# Sheet1.net
KiCad netlist of a schematic drawn in Altium Designer
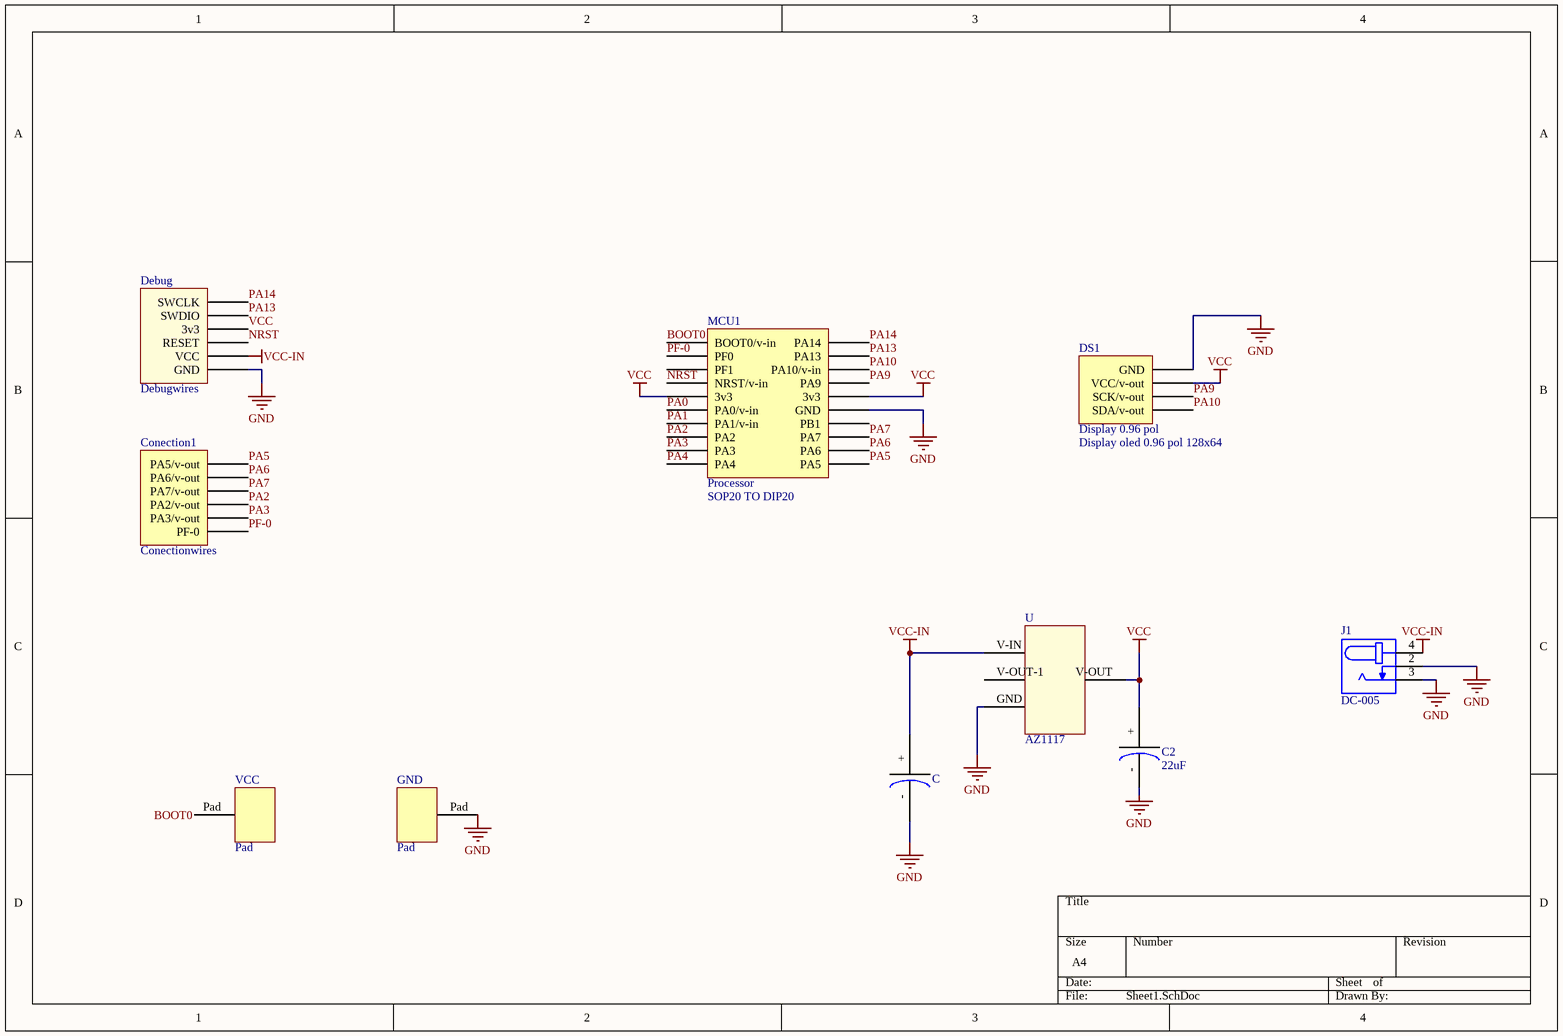
[diagram p0: Sheet1.SchDoc]

(export (version "E")
  (design (tool "Eeschema 10.0.6"))
  (components
    (comp (ref "C")
      (value "Capacitor Eletrolítico")
      (footprint "Capacitor")
      (libsource (lib "Schlib1") (part "Capacitor Eletrolítico"))
    )
    (comp (ref "C2")
      (value "22uF")
      (footprint "Capacitor")
      (libsource (lib "Schlib1") (part "Capacitor Eletrolítico"))
    )
    (comp (ref "Conection1")
      (value "Conectionwires")
      (footprint "Conectionwires")
      (description "6 out")
      (libsource (lib "Schlib1") (part "Conectionwires"))
    )
    (comp (ref "Debug")
      (value "Debugwires")
      (footprint "Debugwires")
      (description "2 in")
      (libsource (lib "Schlib1") (part "Debugwires"))
    )
    (comp (ref "DS1")
      (value "Display 0.96 pol")
      (footprint "Display oled")
      (description "0.96 pol 24.7x27 cm")
      (fields (field (name "INFORMATIONS") "Display oled 0.96 pol 128x64"))
      (libsource (lib "Schlib1") (part "Display oled"))
    )
    (comp (ref "GND") (value "Pad") (footprint "Pad") (libsource (lib "") (part "Pad_1")))
    (comp (ref "J1")
      (value "DC-005")
      (footprint "NINIGI_DC-005")
      (description "Polymeric PTC Resettable Fuse 15V 50mA Ih Surface Mount 0603 _1608 Metric_, Concave")
      (fields (field (name "MF") "Littelfuse Inc."))
      (libsource (lib "Schlib1") (part "DC-005"))
    )
    (comp (ref "MCU1")
      (value "Processor")
      (footprint "Processor")
      (description "Processor arm Stm32f0xx")
      (fields (field (name "ADAPTER") "SOP20 TO DIP20"))
      (libsource (lib "Schlib1") (part "Processor"))
    )
    (comp (ref "U")
      (value "AZ1117")
      (footprint "AZ1117")
      (description "Converter 5v to 3.3v")
      (libsource (lib "Schlib1") (part "AZ1117"))
    )
    (comp (ref "VCC") (value "Pad") (footprint "Pad") (libsource (lib "Schlib1") (part "Pad")))
  )
  (nets
    (net (code "1") (name "/BOOT0") (class "Default")
      (node (ref "MCU1") (pin "BOOT0") (pinfunction "BOOT0/v-in_BOOT0") (pintype "passive"))
      (node (ref "VCC") (pin "Pad") (pinfunction "Pad_Pad") (pintype "passive"))
    )
    (net (code "2") (name "/NRST") (class "Default")
      (node (ref "Debug") (pin "RESET") (pinfunction "RESET_RESET") (pintype "passive"))
      (node (ref "MCU1") (pin "NRST") (pinfunction "NRST/v-in_NRST") (pintype "passive"))
    )
    (net (code "3") (name "/PA0") (class "Default")
      (node (ref "MCU1") (pin "PA0") (pinfunction "PA0/v-in_PA0") (pintype "passive"))
    )
    (net (code "4") (name "/PA1") (class "Default")
      (node (ref "MCU1") (pin "PA1") (pinfunction "PA1/v-in_PA1") (pintype "passive"))
    )
    (net (code "5") (name "/PA2") (class "Default")
      (node (ref "Conection1") (pin "PA2") (pinfunction "PA2/v-out_PA2") (pintype "passive"))
      (node (ref "MCU1") (pin "PA2") (pinfunction "PA2_PA2") (pintype "passive"))
    )
    (net (code "6") (name "/PA3") (class "Default")
      (node (ref "Conection1") (pin "PA3") (pinfunction "PA3/v-out_PA3") (pintype "passive"))
      (node (ref "MCU1") (pin "PA3") (pinfunction "PA3_PA3") (pintype "passive"))
    )
    (net (code "7") (name "/PA4") (class "Default")
      (node (ref "MCU1") (pin "PA4") (pinfunction "PA4_PA4") (pintype "passive"))
    )
    (net (code "8") (name "/PA5") (class "Default")
      (node (ref "Conection1") (pin "PA5") (pinfunction "PA5/v-out_PA5") (pintype "passive"))
      (node (ref "MCU1") (pin "PA5") (pinfunction "PA5_PA5") (pintype "passive"))
    )
    (net (code "9") (name "/PA6") (class "Default")
      (node (ref "Conection1") (pin "PA6") (pinfunction "PA6/v-out_PA6") (pintype "passive"))
      (node (ref "MCU1") (pin "PA6") (pinfunction "PA6_PA6") (pintype "passive"))
    )
    (net (code "10") (name "/PA7") (class "Default")
      (node (ref "Conection1") (pin "PA7") (pinfunction "PA7/v-out_PA7") (pintype "passive"))
      (node (ref "MCU1") (pin "PA7") (pinfunction "PA7_PA7") (pintype "passive"))
    )
    (net (code "11") (name "/PA9") (class "Default")
      (node (ref "DS1") (pin "SCK") (pinfunction "SCK/v-out_SCK") (pintype "passive"))
      (node (ref "MCU1") (pin "PA9") (pinfunction "PA9_PA9") (pintype "passive"))
    )
    (net (code "12") (name "/PA10") (class "Default")
      (node (ref "DS1") (pin "SDA") (pinfunction "SDA/v-out_SDA") (pintype "passive"))
      (node (ref "MCU1") (pin "PA10") (pinfunction "PA10/v-in_PA10") (pintype "passive"))
    )
    (net (code "13") (name "/PA13") (class "Default")
      (node (ref "Debug") (pin "PA13") (pinfunction "SWDIO_PA13") (pintype "passive"))
      (node (ref "MCU1") (pin "PA13") (pinfunction "PA13_PA13") (pintype "passive"))
    )
    (net (code "14") (name "/PA14") (class "Default")
      (node (ref "Debug") (pin "PA14") (pinfunction "SWCLK_PA14") (pintype "passive"))
      (node (ref "MCU1") (pin "PA14") (pinfunction "PA14_PA14") (pintype "passive"))
    )
    (net (code "15") (name "/PF-0") (class "Default")
      (node (ref "Conection1") (pin "PF-0") (pinfunction "PF-0_PF-0") (pintype "passive"))
      (node (ref "MCU1") (pin "PF0") (pinfunction "PF0_PF0") (pintype "passive"))
    )
    (net (code "16") (name "GND") (class "Default")
      (node (ref "C") (pin "-") (pinfunction "-_-") (pintype "passive"))
      (node (ref "C2") (pin "-") (pinfunction "-_-") (pintype "passive"))
      (node (ref "DS1") (pin "GND") (pinfunction "GND_GND") (pintype "passive"))
      (node (ref "Debug") (pin "GND") (pinfunction "GND_GND") (pintype "passive"))
      (node (ref "GND") (pin "Pad") (pinfunction "Pad_Pad") (pintype "passive"))
      (node (ref "J1") (pin "2") (pinfunction "4_2") (pintype "passive"))
      (node (ref "J1") (pin "3") (pinfunction "3_3") (pintype "passive"))
      (node (ref "MCU1") (pin "GND") (pinfunction "GND_GND") (pintype "passive"))
      (node (ref "U") (pin "GND") (pinfunction "GND_GND") (pintype "passive"))
    )
    (net (code "17") (name "VCC") (class "Default")
      (node (ref "C2") (pin "+") (pinfunction "+_+") (pintype "passive"))
      (node (ref "DS1") (pin "VCC") (pinfunction "VCC/v-out_VCC") (pintype "passive"))
      (node (ref "Debug") (pin "3v3") (pinfunction "3v3_3v3") (pintype "passive"))
      (node (ref "MCU1") (pin "3v3") (pinfunction "3v3_3v3") (pintype "passive"))
      (node (ref "U") (pin "V-OUT") (pinfunction "V-OUT_V-OUT") (pintype "passive"))
    )
    (net (code "18") (name "VCC-IN") (class "Default")
      (node (ref "C") (pin "+") (pinfunction "+_+") (pintype "passive"))
      (node (ref "Debug") (pin "VCC") (pinfunction "VCC_VCC") (pintype "passive"))
      (node (ref "J1") (pin "4") (pinfunction "2_4") (pintype "passive"))
      (node (ref "U") (pin "V-IN") (pinfunction "V-IN_V-IN") (pintype "passive"))
    )
    (net (code "19") (name "unconnected-(MCU1-PadPB1)") (class "Default")
      (node (ref "MCU1") (pin "PB1") (pinfunction "PB1_PB1") (pintype "passive"))
    )
    (net (code "20") (name "unconnected-(MCU1-PadPF1)") (class "Default")
      (node (ref "MCU1") (pin "PF1") (pinfunction "PF1_PF1") (pintype "passive"))
    )
    (net (code "21") (name "unconnected-(U-PadV-OUT-1)") (class "Default")
      (node (ref "U") (pin "V-OUT-1") (pinfunction "V-OUT-1_V-OUT-1") (pintype "passive"))
    )
  )
)
